# x-IMU3-SA-Light.net
KiCad netlist of a schematic drawn in Altium Designer
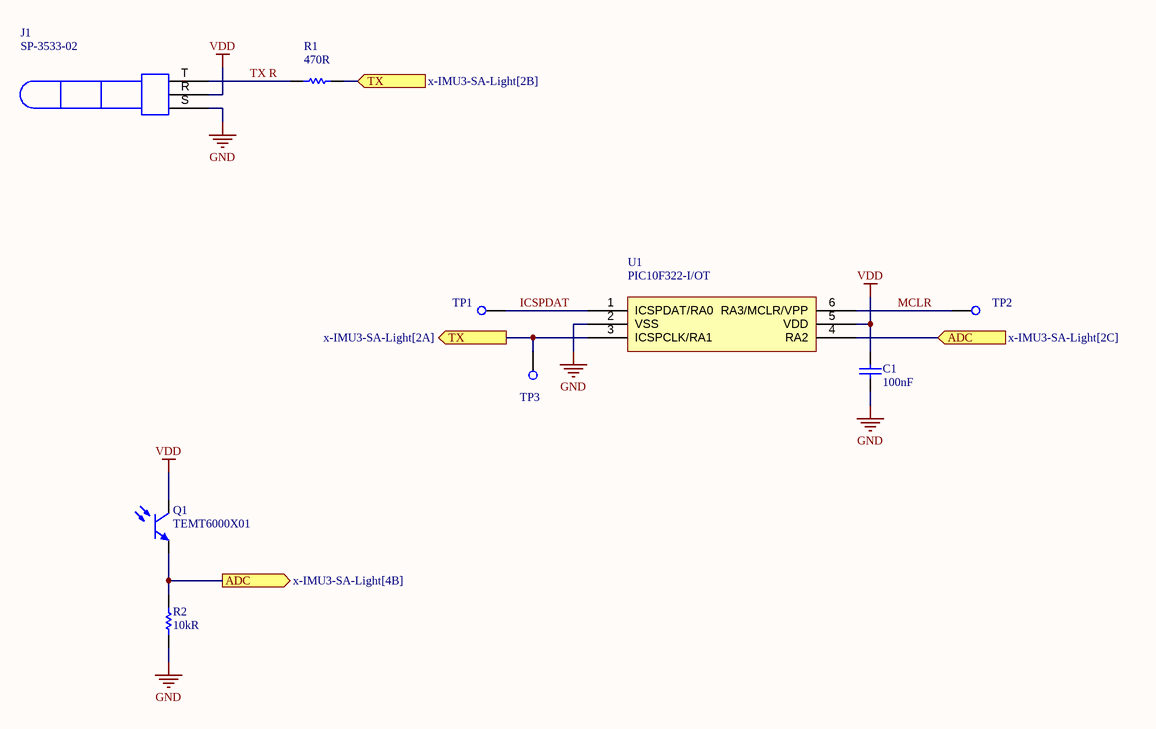
[diagram p0: x-IMU3-SA-Light.SchDoc]

(export (version "E")
  (design (tool "Eeschema 10.0.6"))
  (components
    (comp (ref "C1") (value "100nF") (footprint "Capacitor 0402") (libsource (lib "x-io") (part "Capacitor")))
    (comp (ref "J1")
      (value "SP-3533-02")
      (footprint "SP-3533-02")
      (libsource (lib "x-io") (part "SP-3533-02"))
    )
    (comp (ref "Q1")
      (value "TEMT6000X01")
      (footprint "TEMT6000X01")
      (libsource (lib "x-io") (part "TEMT6000X01"))
    )
    (comp (ref "R1") (value "470R") (footprint "Resistor 0402") (libsource (lib "x-io") (part "Resistor")))
    (comp (ref "R2") (value "10kR") (footprint "Resistor 0402") (libsource (lib "x-io") (part "Resistor")))
    (comp (ref "TP1")
      (value "Test Point")
      (footprint "Test Point 1mm")
      (libsource (lib "x-io") (part "Test Point"))
    )
    (comp (ref "TP2")
      (value "Test Point")
      (footprint "Test Point 1mm")
      (libsource (lib "x-io") (part "Test Point"))
    )
    (comp (ref "TP3")
      (value "Test Point")
      (footprint "Test Point 1mm")
      (libsource (lib "x-io") (part "Test Point"))
    )
    (comp (ref "U1")
      (value "PIC10F322-I/OT")
      (footprint "SOT-23-6")
      (libsource (lib "x-io") (part "PIC10F322-I/OT"))
    )
  )
  (nets
    (net (code "1") (name "/ADC") (class "Default")
      (node (ref "Q1") (pin "Emitter") (pinfunction "Emitter_Emitter") (pintype "passive"))
      (node (ref "R2") (pin "2") (pinfunction "2_2") (pintype "passive"))
      (node (ref "U1") (pin "4") (pinfunction "RA2_4") (pintype "passive"))
    )
    (net (code "2") (name "/ICSPDAT") (class "Default")
      (node (ref "TP1") (pin "1") (pinfunction "1_1") (pintype "passive"))
      (node (ref "U1") (pin "1") (pinfunction "ICSPDAT/RA0_1") (pintype "passive"))
    )
    (net (code "3") (name "/MCLR") (class "Default")
      (node (ref "TP2") (pin "1") (pinfunction "1_1") (pintype "passive"))
      (node (ref "U1") (pin "6") (pinfunction "RA3/MCLR/VPP_6") (pintype "passive"))
    )
    (net (code "4") (name "/TX") (class "Default")
      (node (ref "R1") (pin "2") (pinfunction "2_2") (pintype "passive"))
      (node (ref "TP3") (pin "1") (pinfunction "1_1") (pintype "passive"))
      (node (ref "U1") (pin "3") (pinfunction "ICSPCLK/RA1_3") (pintype "passive"))
    )
    (net (code "5") (name "/TX R") (class "Default")
      (node (ref "J1") (pin "T") (pinfunction "T_T") (pintype "passive"))
      (node (ref "R1") (pin "1") (pinfunction "1_1") (pintype "passive"))
    )
    (net (code "6") (name "GND") (class "Default")
      (node (ref "C1") (pin "1") (pinfunction "1_1") (pintype "passive"))
      (node (ref "J1") (pin "S") (pinfunction "S_S") (pintype "passive"))
      (node (ref "R2") (pin "1") (pinfunction "1_1") (pintype "passive"))
      (node (ref "U1") (pin "2") (pinfunction "VSS_2") (pintype "passive"))
    )
    (net (code "7") (name "VDD") (class "Default")
      (node (ref "C1") (pin "2") (pinfunction "2_2") (pintype "passive"))
      (node (ref "J1") (pin "R") (pinfunction "R_R") (pintype "passive"))
      (node (ref "Q1") (pin "Collector") (pinfunction "Collector_Collector") (pintype "passive"))
      (node (ref "U1") (pin "5") (pinfunction "VDD_5") (pintype "passive"))
    )
  )
)
